# sonic_screwdriver_lipo.net
KiCad netlist of a schematic drawn in EAGLE
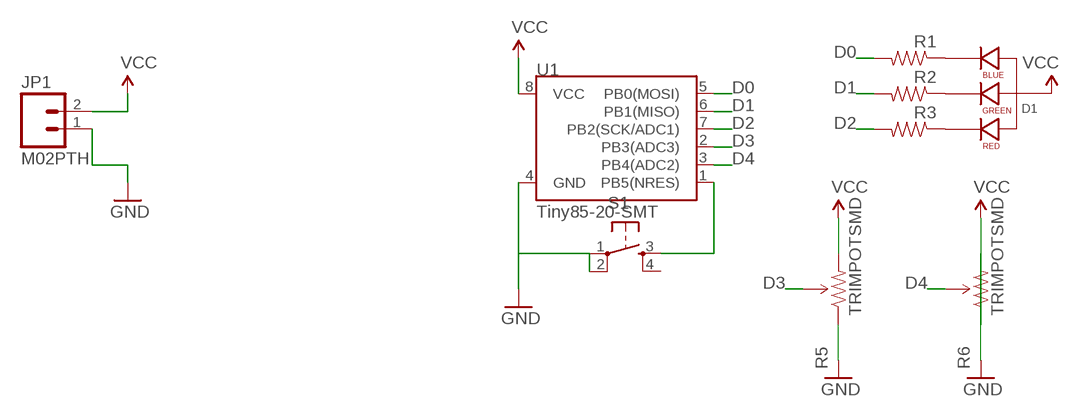
[diagram p0: schematic, sheet 1]

(export (version "E")
  (design (tool "Eeschema 10.0.6"))
  (components
    (comp (ref "D1")
      (value "LED-RGB-CA-THRUEDGE")
      (footprint "eagle-import:LED-RGB-EDGE")
      (libsource (lib "eagle-import") (part "LED-RGB-CA-THRUEDGE"))
    )
    (comp (ref "JP1")
      (value "M02PTH")
      (footprint "eagle-import:1X02")
      (libsource (lib "eagle-import") (part "M02PTH"))
    )
    (comp (ref "R1")
      (value "RESISTOR0805-RES")
      (footprint "eagle-import:0805")
      (libsource (lib "eagle-import") (part "RESISTOR0805-RES"))
    )
    (comp (ref "R2")
      (value "RESISTOR0805-RES")
      (footprint "eagle-import:0805")
      (libsource (lib "eagle-import") (part "RESISTOR0805-RES"))
    )
    (comp (ref "R3")
      (value "RESISTOR0805-RES")
      (footprint "eagle-import:0805")
      (libsource (lib "eagle-import") (part "RESISTOR0805-RES"))
    )
    (comp (ref "R5")
      (value "TRIMPOTSMD")
      (footprint "eagle-import:TRIMPOT-3MM")
      (libsource (lib "eagle-import") (part "TRIMPOTSMD"))
    )
    (comp (ref "R6")
      (value "TRIMPOTSMD")
      (footprint "eagle-import:TRIMPOT-3MM")
      (libsource (lib "eagle-import") (part "TRIMPOTSMD"))
    )
    (comp (ref "S1")
      (value "TAC_SWITCHSMD")
      (footprint "eagle-import:TACTILE-SWITCH-SMD")
      (libsource (lib "eagle-import") (part "TAC_SWITCHSMD"))
    )
    (comp (ref "U1")
      (value "Tiny85-20-SMT")
      (footprint "eagle-import:SO08-EIAJ")
      (libsource (lib "eagle-import") (part "ATTINY45TINY85-20-SMT"))
    )
  )
  (nets
    (net (code "1") (name "/D0") (class "Default")
      (node (ref "R1") (pin "2") (pinfunction "2_2") (pintype "passive"))
      (node (ref "U1") (pin "5") (pinfunction "PB0(MOSI)_5") (pintype "bidirectional"))
    )
    (net (code "2") (name "/D1") (class "Default")
      (node (ref "R2") (pin "2") (pinfunction "2_2") (pintype "passive"))
      (node (ref "U1") (pin "6") (pinfunction "PB1(MISO)_6") (pintype "bidirectional"))
    )
    (net (code "3") (name "/D2") (class "Default")
      (node (ref "R3") (pin "2") (pinfunction "2_2") (pintype "passive"))
      (node (ref "U1") (pin "7") (pinfunction "PB2(SCK/ADC1)_7") (pintype "bidirectional"))
    )
    (net (code "4") (name "/D3") (class "Default")
      (node (ref "R5") (pin "2") (pinfunction "WIPER_2") (pintype "passive"))
      (node (ref "U1") (pin "2") (pinfunction "PB3(ADC3)_2") (pintype "bidirectional"))
    )
    (net (code "5") (name "/D4") (class "Default")
      (node (ref "R6") (pin "2") (pinfunction "WIPER_2") (pintype "passive"))
      (node (ref "U1") (pin "3") (pinfunction "PB4(ADC2)_3") (pintype "bidirectional"))
    )
    (net (code "6") (name "GND") (class "Default")
      (node (ref "JP1") (pin "1") (pinfunction "1_1") (pintype "passive"))
      (node (ref "R5") (pin "1") (pinfunction "CCW_1") (pintype "passive"))
      (node (ref "R6") (pin "3") (pinfunction "CW_3") (pintype "passive"))
      (node (ref "S1") (pin "1") (pinfunction "1_1") (pintype "passive"))
      (node (ref "S1") (pin "2") (pinfunction "2_2") (pintype "passive"))
      (node (ref "U1") (pin "4") (pinfunction "GND_4") (pintype "bidirectional"))
    )
    (net (code "7") (name "Net-(D1-BLUE_CATHODE)") (class "Default")
      (node (ref "D1") (pin "4") (pinfunction "BLUE_CATHODE_4") (pintype "bidirectional"))
      (node (ref "R1") (pin "1") (pinfunction "1_1") (pintype "passive"))
    )
    (net (code "8") (name "Net-(D1-GREEN_CATHODE)") (class "Default")
      (node (ref "D1") (pin "3") (pinfunction "GREEN_CATHODE_3") (pintype "bidirectional"))
      (node (ref "R2") (pin "1") (pinfunction "1_1") (pintype "passive"))
    )
    (net (code "9") (name "Net-(D1-RED_CATHODE)") (class "Default")
      (node (ref "D1") (pin "1") (pinfunction "RED_CATHODE_1") (pintype "bidirectional"))
      (node (ref "R3") (pin "1") (pinfunction "1_1") (pintype "passive"))
    )
    (net (code "10") (name "Net-(U1-PB5(NRES))") (class "Default")
      (node (ref "S1") (pin "3") (pinfunction "3_3") (pintype "passive"))
      (node (ref "U1") (pin "1") (pinfunction "PB5(NRES)_1") (pintype "bidirectional"))
    )
    (net (code "11") (name "VCC") (class "Default")
      (node (ref "D1") (pin "2") (pinfunction "ANODE_2") (pintype "bidirectional"))
      (node (ref "JP1") (pin "2") (pinfunction "2_2") (pintype "passive"))
      (node (ref "R5") (pin "3") (pinfunction "CW_3") (pintype "passive"))
      (node (ref "R6") (pin "1") (pinfunction "CCW_1") (pintype "passive"))
      (node (ref "U1") (pin "8") (pinfunction "VCC_8") (pintype "bidirectional"))
    )
    (net (code "12") (name "unconnected-(S1-Pad4)") (class "Default")
      (node (ref "S1") (pin "4") (pinfunction "4_4") (pintype "passive"))
    )
  )
)
